# pickit2_clone.net
KiCad netlist of a schematic drawn in EAGLE
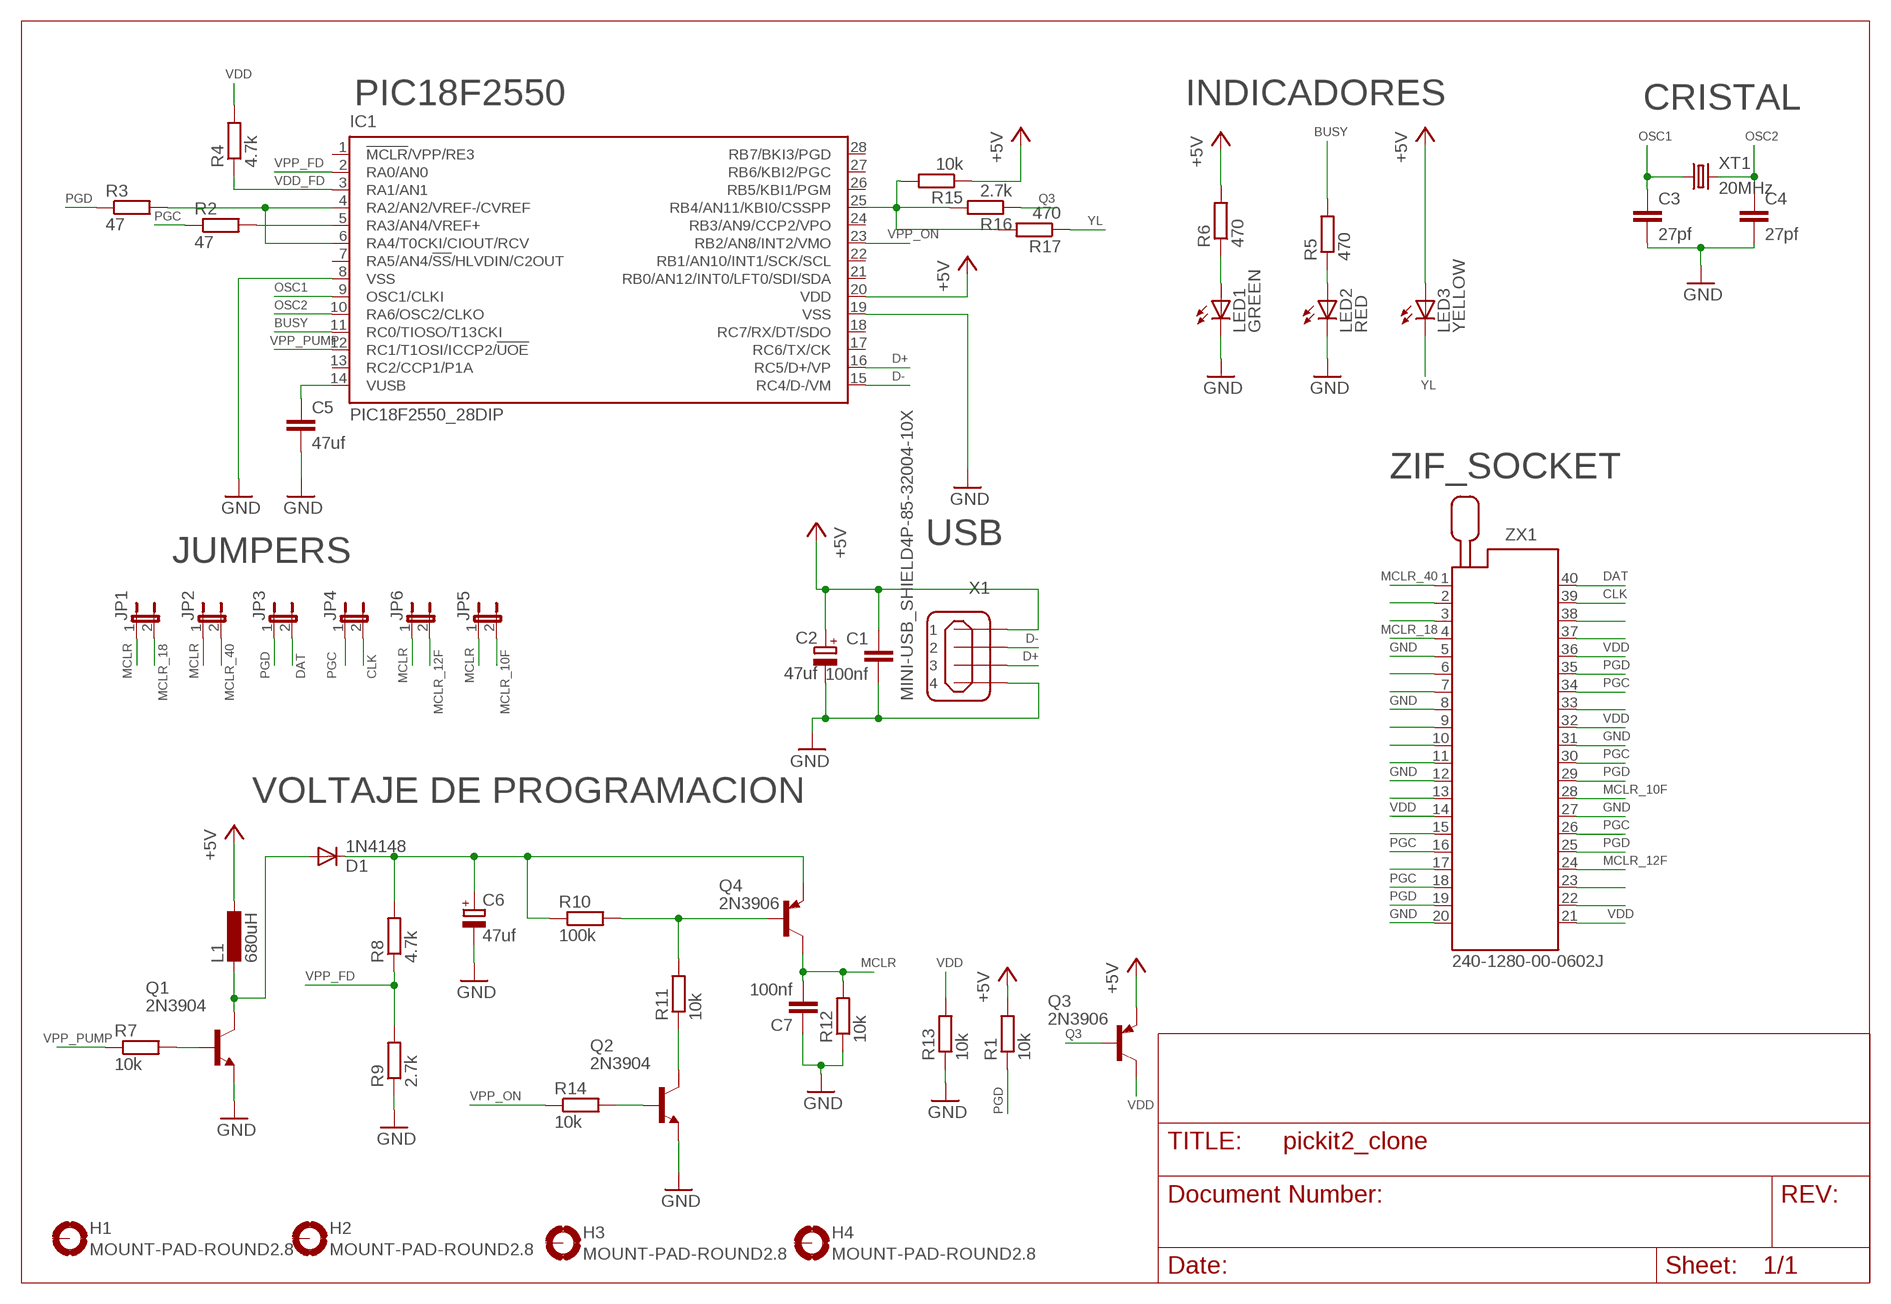
[diagram p0: schematic, sheet 1]

(export (version "E")
  (design (tool "Eeschema 10.0.6"))
  (components
    (comp (ref "C1")
      (value "100nf")
      (footprint "eagle-import:C025-030X050")
      (libsource (lib "eagle-import") (part "C-EU025-030X050"))
    )
    (comp (ref "C2")
      (value "47uf")
      (footprint "eagle-import:E2-5")
      (libsource (lib "eagle-import") (part "CPOL-EUE2-5"))
    )
    (comp (ref "C3")
      (value "27pf")
      (footprint "eagle-import:C050-030X075")
      (libsource (lib "eagle-import") (part "C-EU050-030X075"))
    )
    (comp (ref "C4")
      (value "27pf")
      (footprint "eagle-import:C050-030X075")
      (libsource (lib "eagle-import") (part "C-EU050-030X075"))
    )
    (comp (ref "C5")
      (value "47uf")
      (footprint "eagle-import:C050-030X075")
      (libsource (lib "eagle-import") (part "C-EU050-030X075"))
    )
    (comp (ref "C6")
      (value "47uf")
      (footprint "eagle-import:E2-5")
      (libsource (lib "eagle-import") (part "CPOL-EUE2-5"))
    )
    (comp (ref "C7")
      (value "100nf")
      (footprint "eagle-import:C025-030X050")
      (libsource (lib "eagle-import") (part "C-EU025-030X050"))
    )
    (comp (ref "D1")
      (value "1N4148")
      (footprint "eagle-import:DO35-10")
      (libsource (lib "eagle-import") (part "1N4148"))
    )
    (comp (ref "H1")
      (value "MOUNT-PAD-ROUND2.8")
      (footprint "eagle-import:2,8-PAD")
      (libsource (lib "eagle-import") (part "MOUNT-PAD-ROUND2.8"))
    )
    (comp (ref "H2")
      (value "MOUNT-PAD-ROUND2.8")
      (footprint "eagle-import:2,8-PAD")
      (libsource (lib "eagle-import") (part "MOUNT-PAD-ROUND2.8"))
    )
    (comp (ref "H3")
      (value "MOUNT-PAD-ROUND2.8")
      (footprint "eagle-import:2,8-PAD")
      (libsource (lib "eagle-import") (part "MOUNT-PAD-ROUND2.8"))
    )
    (comp (ref "H4")
      (value "MOUNT-PAD-ROUND2.8")
      (footprint "eagle-import:2,8-PAD")
      (libsource (lib "eagle-import") (part "MOUNT-PAD-ROUND2.8"))
    )
    (comp (ref "IC1")
      (value "PIC18F2550_28DIP")
      (footprint "eagle-import:DIL28-3")
      (libsource (lib "eagle-import") (part "PIC18F2_28DIP550"))
    )
    (comp (ref "JP1")
      (value "JP1E")
      (footprint "eagle-import:JP1")
      (libsource (lib "eagle-import") (part "JP1E"))
    )
    (comp (ref "JP2")
      (value "JP1E")
      (footprint "eagle-import:JP1")
      (libsource (lib "eagle-import") (part "JP1E"))
    )
    (comp (ref "JP3")
      (value "JP1E")
      (footprint "eagle-import:JP1")
      (libsource (lib "eagle-import") (part "JP1E"))
    )
    (comp (ref "JP4")
      (value "JP1E")
      (footprint "eagle-import:JP1")
      (libsource (lib "eagle-import") (part "JP1E"))
    )
    (comp (ref "JP5")
      (value "JP1E")
      (footprint "eagle-import:JP1")
      (libsource (lib "eagle-import") (part "JP1E"))
    )
    (comp (ref "JP6")
      (value "JP1E")
      (footprint "eagle-import:JP1")
      (libsource (lib "eagle-import") (part "JP1E"))
    )
    (comp (ref "L1")
      (value "680uH")
      (footprint "eagle-import:0207_10")
      (libsource (lib "eagle-import") (part "L-EU0207/10"))
    )
    (comp (ref "LED1")
      (value "GREEN")
      (footprint "eagle-import:LED5MM")
      (libsource (lib "eagle-import") (part "LED5MM"))
    )
    (comp (ref "LED2")
      (value "RED")
      (footprint "eagle-import:LED5MM")
      (libsource (lib "eagle-import") (part "LED5MM"))
    )
    (comp (ref "LED3")
      (value "YELLOW")
      (footprint "eagle-import:LED5MM")
      (libsource (lib "eagle-import") (part "LED5MM"))
    )
    (comp (ref "Q1")
      (value "2N3904")
      (footprint "eagle-import:TO92-EBC")
      (libsource (lib "eagle-import") (part "BC447"))
    )
    (comp (ref "Q2")
      (value "2N3904")
      (footprint "eagle-import:TO92-EBC")
      (libsource (lib "eagle-import") (part "BC489"))
    )
    (comp (ref "Q3")
      (value "2N3906")
      (footprint "eagle-import:TO92-CBE")
      (libsource (lib "eagle-import") (part "2N4126"))
    )
    (comp (ref "Q4")
      (value "2N3906")
      (footprint "eagle-import:TO92-CBE")
      (libsource (lib "eagle-import") (part "2N4126"))
    )
    (comp (ref "R1")
      (value "10k")
      (footprint "eagle-import:0207_7")
      (libsource (lib "eagle-import") (part "R-EU_0207/7"))
    )
    (comp (ref "R2")
      (value "47")
      (footprint "eagle-import:0207_7")
      (libsource (lib "eagle-import") (part "R-EU_0207/7"))
    )
    (comp (ref "R3")
      (value "47")
      (footprint "eagle-import:0207_7")
      (libsource (lib "eagle-import") (part "R-EU_0207/7"))
    )
    (comp (ref "R4")
      (value "4.7k")
      (footprint "eagle-import:0207_7")
      (libsource (lib "eagle-import") (part "R-EU_0207/7"))
    )
    (comp (ref "R5")
      (value "470")
      (footprint "eagle-import:0207_7")
      (libsource (lib "eagle-import") (part "R-EU_0207/7"))
    )
    (comp (ref "R6")
      (value "470")
      (footprint "eagle-import:0207_7")
      (libsource (lib "eagle-import") (part "R-EU_0207/7"))
    )
    (comp (ref "R7")
      (value "10k")
      (footprint "eagle-import:0207_7")
      (libsource (lib "eagle-import") (part "R-EU_0207/7"))
    )
    (comp (ref "R8")
      (value "4.7k")
      (footprint "eagle-import:0207_7")
      (libsource (lib "eagle-import") (part "R-EU_0207/7"))
    )
    (comp (ref "R9")
      (value "2.7k")
      (footprint "eagle-import:0207_7")
      (libsource (lib "eagle-import") (part "R-EU_0207/7"))
    )
    (comp (ref "R10")
      (value "100k")
      (footprint "eagle-import:0207_7")
      (libsource (lib "eagle-import") (part "R-EU_0207/7"))
    )
    (comp (ref "R11")
      (value "10k")
      (footprint "eagle-import:0207_7")
      (libsource (lib "eagle-import") (part "R-EU_0207/7"))
    )
    (comp (ref "R12")
      (value "10k")
      (footprint "eagle-import:0207_7")
      (libsource (lib "eagle-import") (part "R-EU_0207/7"))
    )
    (comp (ref "R13")
      (value "10k")
      (footprint "eagle-import:0207_7")
      (libsource (lib "eagle-import") (part "R-EU_0207/7"))
    )
    (comp (ref "R14")
      (value "10k")
      (footprint "eagle-import:0207_7")
      (libsource (lib "eagle-import") (part "R-EU_0207/7"))
    )
    (comp (ref "R15")
      (value "10k")
      (footprint "eagle-import:0207_7")
      (libsource (lib "eagle-import") (part "R-EU_0207/7"))
    )
    (comp (ref "R16")
      (value "2.7k")
      (footprint "eagle-import:0207_7")
      (libsource (lib "eagle-import") (part "R-EU_0207/7"))
    )
    (comp (ref "R17")
      (value "470")
      (footprint "eagle-import:0207_7")
      (libsource (lib "eagle-import") (part "R-EU_0207/7"))
    )
    (comp (ref "X1")
      (value "MINI-USB_SHIELD4P-85-32004-10X")
      (footprint "eagle-import:85-32004-10X")
      (libsource (lib "eagle-import") (part "MINI-USB_SHIELD4P-85-32004-10X"))
    )
    (comp (ref "XT1")
      (value "20MHz")
      (footprint "eagle-import:HC49_S")
      (libsource (lib "eagle-import") (part "CRYSTALHC49S"))
    )
    (comp (ref "ZX1")
      (value "240-1280-00-0602J")
      (footprint "eagle-import:240-1280-00-0602J")
      (libsource (lib "eagle-import") (part "240-?-00-0602J1280"))
    )
  )
  (nets
    (net (code "1") (name "+5V") (class "Default")
      (node (ref "C1") (pin "1") (pinfunction "1_1") (pintype "passive"))
      (node (ref "C2") (pin "+") (pinfunction "+_+") (pintype "passive"))
      (node (ref "IC1") (pin "20") (pinfunction "VDD_20") (pintype "power_in"))
      (node (ref "L1") (pin "1") (pinfunction "1_1") (pintype "passive"))
      (node (ref "LED3") (pin "A") (pinfunction "A_A") (pintype "passive"))
      (node (ref "Q3") (pin "E") (pinfunction "E_E") (pintype "passive"))
      (node (ref "R1") (pin "2") (pinfunction "2_2") (pintype "passive"))
      (node (ref "R15") (pin "1") (pinfunction "1_1") (pintype "passive"))
      (node (ref "R6") (pin "2") (pinfunction "2_2") (pintype "passive"))
      (node (ref "X1") (pin "1") (pinfunction "1_1") (pintype "passive"))
    )
    (net (code "2") (name "/BUSY") (class "Default")
      (node (ref "IC1") (pin "11") (pinfunction "RC0/TIOSO/T13CKI_11") (pintype "bidirectional"))
      (node (ref "R5") (pin "2") (pinfunction "2_2") (pintype "passive"))
    )
    (net (code "3") (name "/CLK") (class "Default")
      (node (ref "JP4") (pin "2") (pinfunction "2_2") (pintype "passive"))
      (node (ref "ZX1") (pin "39") (pinfunction "39_39") (pintype "passive"))
    )
    (net (code "4") (name "/D+") (class "Default")
      (node (ref "IC1") (pin "16") (pinfunction "RC5/D+/VP_16") (pintype "bidirectional"))
      (node (ref "X1") (pin "3") (pinfunction "3_3") (pintype "passive"))
    )
    (net (code "5") (name "/D-") (class "Default")
      (node (ref "IC1") (pin "15") (pinfunction "RC4/D-/VM_15") (pintype "bidirectional"))
      (node (ref "X1") (pin "2") (pinfunction "2_2") (pintype "passive"))
    )
    (net (code "6") (name "/DAT") (class "Default")
      (node (ref "JP3") (pin "2") (pinfunction "2_2") (pintype "passive"))
      (node (ref "ZX1") (pin "40") (pinfunction "40_40") (pintype "passive"))
    )
    (net (code "7") (name "/MCLR") (class "Default")
      (node (ref "C7") (pin "2") (pinfunction "2_2") (pintype "passive"))
      (node (ref "JP1") (pin "1") (pinfunction "1_1") (pintype "passive"))
      (node (ref "JP2") (pin "1") (pinfunction "1_1") (pintype "passive"))
      (node (ref "JP5") (pin "1") (pinfunction "1_1") (pintype "passive"))
      (node (ref "JP6") (pin "1") (pinfunction "1_1") (pintype "passive"))
      (node (ref "Q4") (pin "C") (pinfunction "C_C") (pintype "passive"))
      (node (ref "R12") (pin "2") (pinfunction "2_2") (pintype "passive"))
    )
    (net (code "8") (name "/MCLR_10F") (class "Default")
      (node (ref "JP5") (pin "2") (pinfunction "2_2") (pintype "passive"))
      (node (ref "ZX1") (pin "28") (pinfunction "28_28") (pintype "passive"))
    )
    (net (code "9") (name "/MCLR_12F") (class "Default")
      (node (ref "JP6") (pin "2") (pinfunction "2_2") (pintype "passive"))
      (node (ref "ZX1") (pin "24") (pinfunction "24_24") (pintype "passive"))
    )
    (net (code "10") (name "/MCLR_18") (class "Default")
      (node (ref "JP1") (pin "2") (pinfunction "2_2") (pintype "passive"))
      (node (ref "ZX1") (pin "4") (pinfunction "4_4") (pintype "passive"))
    )
    (net (code "11") (name "/MCLR_40") (class "Default")
      (node (ref "JP2") (pin "2") (pinfunction "2_2") (pintype "passive"))
      (node (ref "ZX1") (pin "1") (pinfunction "1_1") (pintype "passive"))
    )
    (net (code "12") (name "/OSC1") (class "Default")
      (node (ref "C3") (pin "1") (pinfunction "1_1") (pintype "passive"))
      (node (ref "IC1") (pin "9") (pinfunction "OSC1/CLKI_9") (pintype "input"))
      (node (ref "XT1") (pin "1") (pinfunction "1_1") (pintype "passive"))
    )
    (net (code "13") (name "/OSC2") (class "Default")
      (node (ref "C4") (pin "1") (pinfunction "1_1") (pintype "passive"))
      (node (ref "IC1") (pin "10") (pinfunction "RA6/OSC2/CLKO_10") (pintype "output"))
      (node (ref "XT1") (pin "2") (pinfunction "2_2") (pintype "passive"))
    )
    (net (code "14") (name "/PGC") (class "Default")
      (node (ref "JP4") (pin "1") (pinfunction "1_1") (pintype "passive"))
      (node (ref "R2") (pin "1") (pinfunction "1_1") (pintype "passive"))
      (node (ref "ZX1") (pin "16") (pinfunction "16_16") (pintype "passive"))
      (node (ref "ZX1") (pin "18") (pinfunction "18_18") (pintype "passive"))
      (node (ref "ZX1") (pin "26") (pinfunction "26_26") (pintype "passive"))
      (node (ref "ZX1") (pin "30") (pinfunction "30_30") (pintype "passive"))
      (node (ref "ZX1") (pin "34") (pinfunction "34_34") (pintype "passive"))
    )
    (net (code "15") (name "/PGD") (class "Default")
      (node (ref "JP3") (pin "1") (pinfunction "1_1") (pintype "passive"))
      (node (ref "R1") (pin "1") (pinfunction "1_1") (pintype "passive"))
      (node (ref "R3") (pin "1") (pinfunction "1_1") (pintype "passive"))
      (node (ref "ZX1") (pin "19") (pinfunction "19_19") (pintype "passive"))
      (node (ref "ZX1") (pin "25") (pinfunction "25_25") (pintype "passive"))
      (node (ref "ZX1") (pin "29") (pinfunction "29_29") (pintype "passive"))
      (node (ref "ZX1") (pin "35") (pinfunction "35_35") (pintype "passive"))
    )
    (net (code "16") (name "/Q3") (class "Default")
      (node (ref "Q3") (pin "B") (pinfunction "B_B") (pintype "passive"))
      (node (ref "R16") (pin "1") (pinfunction "1_1") (pintype "passive"))
    )
    (net (code "17") (name "/VDD") (class "Default")
      (node (ref "Q3") (pin "C") (pinfunction "C_C") (pintype "passive"))
      (node (ref "R13") (pin "2") (pinfunction "2_2") (pintype "passive"))
      (node (ref "R4") (pin "2") (pinfunction "2_2") (pintype "passive"))
      (node (ref "ZX1") (pin "14") (pinfunction "14_14") (pintype "passive"))
      (node (ref "ZX1") (pin "21") (pinfunction "21_21") (pintype "passive"))
      (node (ref "ZX1") (pin "32") (pinfunction "32_32") (pintype "passive"))
      (node (ref "ZX1") (pin "36") (pinfunction "36_36") (pintype "passive"))
    )
    (net (code "18") (name "/VDD_FD") (class "Default")
      (node (ref "IC1") (pin "3") (pinfunction "RA1/AN1_3") (pintype "bidirectional"))
      (node (ref "R4") (pin "1") (pinfunction "1_1") (pintype "passive"))
    )
    (net (code "19") (name "/VPP_FD") (class "Default")
      (node (ref "IC1") (pin "2") (pinfunction "RA0/AN0_2") (pintype "bidirectional"))
      (node (ref "R8") (pin "1") (pinfunction "1_1") (pintype "passive"))
      (node (ref "R9") (pin "2") (pinfunction "2_2") (pintype "passive"))
    )
    (net (code "20") (name "/VPP_ON") (class "Default")
      (node (ref "IC1") (pin "23") (pinfunction "RB2/AN8/INT2/VMO_23") (pintype "bidirectional"))
      (node (ref "R14") (pin "1") (pinfunction "1_1") (pintype "passive"))
    )
    (net (code "21") (name "/VPP_PUMP") (class "Default")
      (node (ref "IC1") (pin "12") (pinfunction "RC1/T1OSI/ICCP2/~{UOE}_12") (pintype "bidirectional"))
      (node (ref "R7") (pin "1") (pinfunction "1_1") (pintype "passive"))
    )
    (net (code "22") (name "/YL") (class "Default")
      (node (ref "LED3") (pin "K") (pinfunction "C_K") (pintype "passive"))
      (node (ref "R17") (pin "1") (pinfunction "1_1") (pintype "passive"))
    )
    (net (code "23") (name "GND") (class "Default")
      (node (ref "C1") (pin "2") (pinfunction "2_2") (pintype "passive"))
      (node (ref "C2") (pin "-") (pinfunction "-_-") (pintype "passive"))
      (node (ref "C3") (pin "2") (pinfunction "2_2") (pintype "passive"))
      (node (ref "C4") (pin "2") (pinfunction "2_2") (pintype "passive"))
      (node (ref "C5") (pin "2") (pinfunction "2_2") (pintype "passive"))
      (node (ref "C6") (pin "-") (pinfunction "-_-") (pintype "passive"))
      (node (ref "C7") (pin "1") (pinfunction "1_1") (pintype "passive"))
      (node (ref "IC1") (pin "19") (pinfunction "VSS_19") (pintype "power_in"))
      (node (ref "IC1") (pin "8") (pinfunction "VSS_8") (pintype "power_in"))
      (node (ref "LED1") (pin "K") (pinfunction "C_K") (pintype "passive"))
      (node (ref "LED2") (pin "K") (pinfunction "C_K") (pintype "passive"))
      (node (ref "Q1") (pin "E") (pinfunction "E_E") (pintype "passive"))
      (node (ref "Q2") (pin "E") (pinfunction "E_E") (pintype "passive"))
      (node (ref "R12") (pin "1") (pinfunction "1_1") (pintype "passive"))
      (node (ref "R13") (pin "1") (pinfunction "1_1") (pintype "passive"))
      (node (ref "R9") (pin "1") (pinfunction "1_1") (pintype "passive"))
      (node (ref "X1") (pin "4") (pinfunction "4_4") (pintype "passive"))
      (node (ref "ZX1") (pin "12") (pinfunction "12_12") (pintype "passive"))
      (node (ref "ZX1") (pin "20") (pinfunction "20_20") (pintype "passive"))
      (node (ref "ZX1") (pin "27") (pinfunction "27_27") (pintype "passive"))
      (node (ref "ZX1") (pin "31") (pinfunction "31_31") (pintype "passive"))
      (node (ref "ZX1") (pin "5") (pinfunction "5_5") (pintype "passive"))
      (node (ref "ZX1") (pin "8") (pinfunction "8_8") (pintype "passive"))
    )
    (net (code "24") (name "Net-(C6-Pad+)") (class "Default")
      (node (ref "C6") (pin "+") (pinfunction "+_+") (pintype "passive"))
      (node (ref "D1") (pin "C") (pinfunction "C_C") (pintype "passive"))
      (node (ref "Q4") (pin "E") (pinfunction "E_E") (pintype "passive"))
      (node (ref "R10") (pin "1") (pinfunction "1_1") (pintype "passive"))
      (node (ref "R8") (pin "2") (pinfunction "2_2") (pintype "passive"))
    )
    (net (code "25") (name "Net-(D1-PadA)") (class "Default")
      (node (ref "D1") (pin "A") (pinfunction "A_A") (pintype "passive"))
      (node (ref "L1") (pin "2") (pinfunction "2_2") (pintype "passive"))
      (node (ref "Q1") (pin "C") (pinfunction "C_C") (pintype "passive"))
    )
    (net (code "26") (name "Net-(IC1-RA2{slash}AN2{slash}VREF-{slash}CVREF)") (class "Default")
      (node (ref "IC1") (pin "4") (pinfunction "RA2/AN2/VREF-/CVREF_4") (pintype "bidirectional"))
      (node (ref "IC1") (pin "6") (pinfunction "RA4/T0CKI/CIOUT/RCV_6") (pintype "bidirectional"))
      (node (ref "R3") (pin "2") (pinfunction "2_2") (pintype "passive"))
    )
    (net (code "27") (name "Net-(IC1-RA3{slash}AN4{slash}VREF+)") (class "Default")
      (node (ref "IC1") (pin "5") (pinfunction "RA3/AN4/VREF+_5") (pintype "bidirectional"))
      (node (ref "R2") (pin "2") (pinfunction "2_2") (pintype "passive"))
    )
    (net (code "28") (name "Net-(IC1-RB4{slash}AN11{slash}KBI0{slash}CSSPP)") (class "Default")
      (node (ref "IC1") (pin "25") (pinfunction "RB4/AN11/KBI0/CSSPP_25") (pintype "bidirectional"))
      (node (ref "R15") (pin "2") (pinfunction "2_2") (pintype "passive"))
      (node (ref "R16") (pin "2") (pinfunction "2_2") (pintype "passive"))
      (node (ref "R17") (pin "2") (pinfunction "2_2") (pintype "passive"))
    )
    (net (code "29") (name "Net-(IC1-VUSB)") (class "Default")
      (node (ref "C5") (pin "1") (pinfunction "1_1") (pintype "passive"))
      (node (ref "IC1") (pin "14") (pinfunction "VUSB_14") (pintype "bidirectional"))
    )
    (net (code "30") (name "Net-(LED1-PadA)") (class "Default")
      (node (ref "LED1") (pin "A") (pinfunction "A_A") (pintype "passive"))
      (node (ref "R6") (pin "1") (pinfunction "1_1") (pintype "passive"))
    )
    (net (code "31") (name "Net-(LED2-PadA)") (class "Default")
      (node (ref "LED2") (pin "A") (pinfunction "A_A") (pintype "passive"))
      (node (ref "R5") (pin "1") (pinfunction "1_1") (pintype "passive"))
    )
    (net (code "32") (name "Net-(Q1-PadB)") (class "Default")
      (node (ref "Q1") (pin "B") (pinfunction "B_B") (pintype "passive"))
      (node (ref "R7") (pin "2") (pinfunction "2_2") (pintype "passive"))
    )
    (net (code "33") (name "Net-(Q2-PadB)") (class "Default")
      (node (ref "Q2") (pin "B") (pinfunction "B_B") (pintype "passive"))
      (node (ref "R14") (pin "2") (pinfunction "2_2") (pintype "passive"))
    )
    (net (code "34") (name "Net-(Q2-PadC)") (class "Default")
      (node (ref "Q2") (pin "C") (pinfunction "C_C") (pintype "passive"))
      (node (ref "R11") (pin "1") (pinfunction "1_1") (pintype "passive"))
    )
    (net (code "35") (name "Net-(Q4-PadB)") (class "Default")
      (node (ref "Q4") (pin "B") (pinfunction "B_B") (pintype "passive"))
      (node (ref "R10") (pin "2") (pinfunction "2_2") (pintype "passive"))
      (node (ref "R11") (pin "2") (pinfunction "2_2") (pintype "passive"))
    )
    (net (code "36") (name "unconnected-(H1-MOUNT-PadB2,8)") (class "Default")
      (node (ref "H1") (pin "B2,8") (pinfunction "MOUNT_B2,8") (pintype "passive"))
    )
    (net (code "37") (name "unconnected-(H2-MOUNT-PadB2,8)") (class "Default")
      (node (ref "H2") (pin "B2,8") (pinfunction "MOUNT_B2,8") (pintype "passive"))
    )
    (net (code "38") (name "unconnected-(H3-MOUNT-PadB2,8)") (class "Default")
      (node (ref "H3") (pin "B2,8") (pinfunction "MOUNT_B2,8") (pintype "passive"))
    )
    (net (code "39") (name "unconnected-(H4-MOUNT-PadB2,8)") (class "Default")
      (node (ref "H4") (pin "B2,8") (pinfunction "MOUNT_B2,8") (pintype "passive"))
    )
    (net (code "40") (name "unconnected-(IC1-RA5{slash}AN4{slash}~{SS}{slash}HLVDIN{slash}C2OUT-Pad7)") (class "Default")
      (node (ref "IC1") (pin "7") (pinfunction "RA5/AN4/~{SS}/HLVDIN/C2OUT_7") (pintype "bidirectional"))
    )
    (net (code "41") (name "unconnected-(IC1-RB0{slash}AN12{slash}INT0{slash}LFT0{slash}SDI{slash}SDA-Pad21)") (class "Default")
      (node (ref "IC1") (pin "21") (pinfunction "RB0/AN12/INT0/LFT0/SDI/SDA_21") (pintype "bidirectional"))
    )
    (net (code "42") (name "unconnected-(IC1-RB1{slash}AN10{slash}INT1{slash}SCK{slash}SCL-Pad22)") (class "Default")
      (node (ref "IC1") (pin "22") (pinfunction "RB1/AN10/INT1/SCK/SCL_22") (pintype "bidirectional"))
    )
    (net (code "43") (name "unconnected-(IC1-RB3{slash}AN9{slash}CCP2{slash}VPO-Pad24)") (class "Default")
      (node (ref "IC1") (pin "24") (pinfunction "RB3/AN9/CCP2/VPO_24") (pintype "bidirectional"))
    )
    (net (code "44") (name "unconnected-(IC1-RB5{slash}KBI1{slash}PGM-Pad26)") (class "Default")
      (node (ref "IC1") (pin "26") (pinfunction "RB5/KBI1/PGM_26") (pintype "bidirectional"))
    )
    (net (code "45") (name "unconnected-(IC1-RB6{slash}KBI2{slash}PGC-Pad27)") (class "Default")
      (node (ref "IC1") (pin "27") (pinfunction "RB6/KBI2/PGC_27") (pintype "bidirectional"))
    )
    (net (code "46") (name "unconnected-(IC1-RB7{slash}BKI3{slash}PGD-Pad28)") (class "Default")
      (node (ref "IC1") (pin "28") (pinfunction "RB7/BKI3/PGD_28") (pintype "bidirectional"))
    )
    (net (code "47") (name "unconnected-(IC1-RC2{slash}CCP1{slash}P1A-Pad13)") (class "Default")
      (node (ref "IC1") (pin "13") (pinfunction "RC2/CCP1/P1A_13") (pintype "bidirectional"))
    )
    (net (code "48") (name "unconnected-(IC1-RC6{slash}TX{slash}CK-Pad17)") (class "Default")
      (node (ref "IC1") (pin "17") (pinfunction "RC6/TX/CK_17") (pintype "bidirectional"))
    )
    (net (code "49") (name "unconnected-(IC1-RC7{slash}RX{slash}DT{slash}SDO-Pad18)") (class "Default")
      (node (ref "IC1") (pin "18") (pinfunction "RC7/RX/DT/SDO_18") (pintype "bidirectional"))
    )
    (net (code "50") (name "unconnected-(IC1-~{MCLR}{slash}VPP{slash}RE3-Pad1)") (class "Default")
      (node (ref "IC1") (pin "1") (pinfunction "~{MCLR}/VPP/RE3_1") (pintype "input"))
    )
    (net (code "51") (name "unconnected-(ZX1-Pad2)") (class "Default")
      (node (ref "ZX1") (pin "2") (pinfunction "2_2") (pintype "passive"))
    )
    (net (code "52") (name "unconnected-(ZX1-Pad3)") (class "Default")
      (node (ref "ZX1") (pin "3") (pinfunction "3_3") (pintype "passive"))
    )
    (net (code "53") (name "unconnected-(ZX1-Pad6)") (class "Default")
      (node (ref "ZX1") (pin "6") (pinfunction "6_6") (pintype "passive"))
    )
    (net (code "54") (name "unconnected-(ZX1-Pad7)") (class "Default")
      (node (ref "ZX1") (pin "7") (pinfunction "7_7") (pintype "passive"))
    )
    (net (code "55") (name "unconnected-(ZX1-Pad9)") (class "Default")
      (node (ref "ZX1") (pin "9") (pinfunction "9_9") (pintype "passive"))
    )
    (net (code "56") (name "unconnected-(ZX1-Pad10)") (class "Default")
      (node (ref "ZX1") (pin "10") (pinfunction "10_10") (pintype "passive"))
    )
    (net (code "57") (name "unconnected-(ZX1-Pad11)") (class "Default")
      (node (ref "ZX1") (pin "11") (pinfunction "11_11") (pintype "passive"))
    )
    (net (code "58") (name "unconnected-(ZX1-Pad13)") (class "Default")
      (node (ref "ZX1") (pin "13") (pinfunction "13_13") (pintype "passive"))
    )
    (net (code "59") (name "unconnected-(ZX1-Pad15)") (class "Default")
      (node (ref "ZX1") (pin "15") (pinfunction "15_15") (pintype "passive"))
    )
    (net (code "60") (name "unconnected-(ZX1-Pad17)") (class "Default")
      (node (ref "ZX1") (pin "17") (pinfunction "17_17") (pintype "passive"))
    )
    (net (code "61") (name "unconnected-(ZX1-Pad22)") (class "Default")
      (node (ref "ZX1") (pin "22") (pinfunction "22_22") (pintype "passive"))
    )
    (net (code "62") (name "unconnected-(ZX1-Pad23)") (class "Default")
      (node (ref "ZX1") (pin "23") (pinfunction "23_23") (pintype "passive"))
    )
    (net (code "63") (name "unconnected-(ZX1-Pad33)") (class "Default")
      (node (ref "ZX1") (pin "33") (pinfunction "33_33") (pintype "passive"))
    )
    (net (code "64") (name "unconnected-(ZX1-Pad37)") (class "Default")
      (node (ref "ZX1") (pin "37") (pinfunction "37_37") (pintype "passive"))
    )
    (net (code "65") (name "unconnected-(ZX1-Pad38)") (class "Default")
      (node (ref "ZX1") (pin "38") (pinfunction "38_38") (pintype "passive"))
    )
  )
)
